# bend_it_board_v_2_F.net
KiCad netlist of a schematic drawn in EAGLE
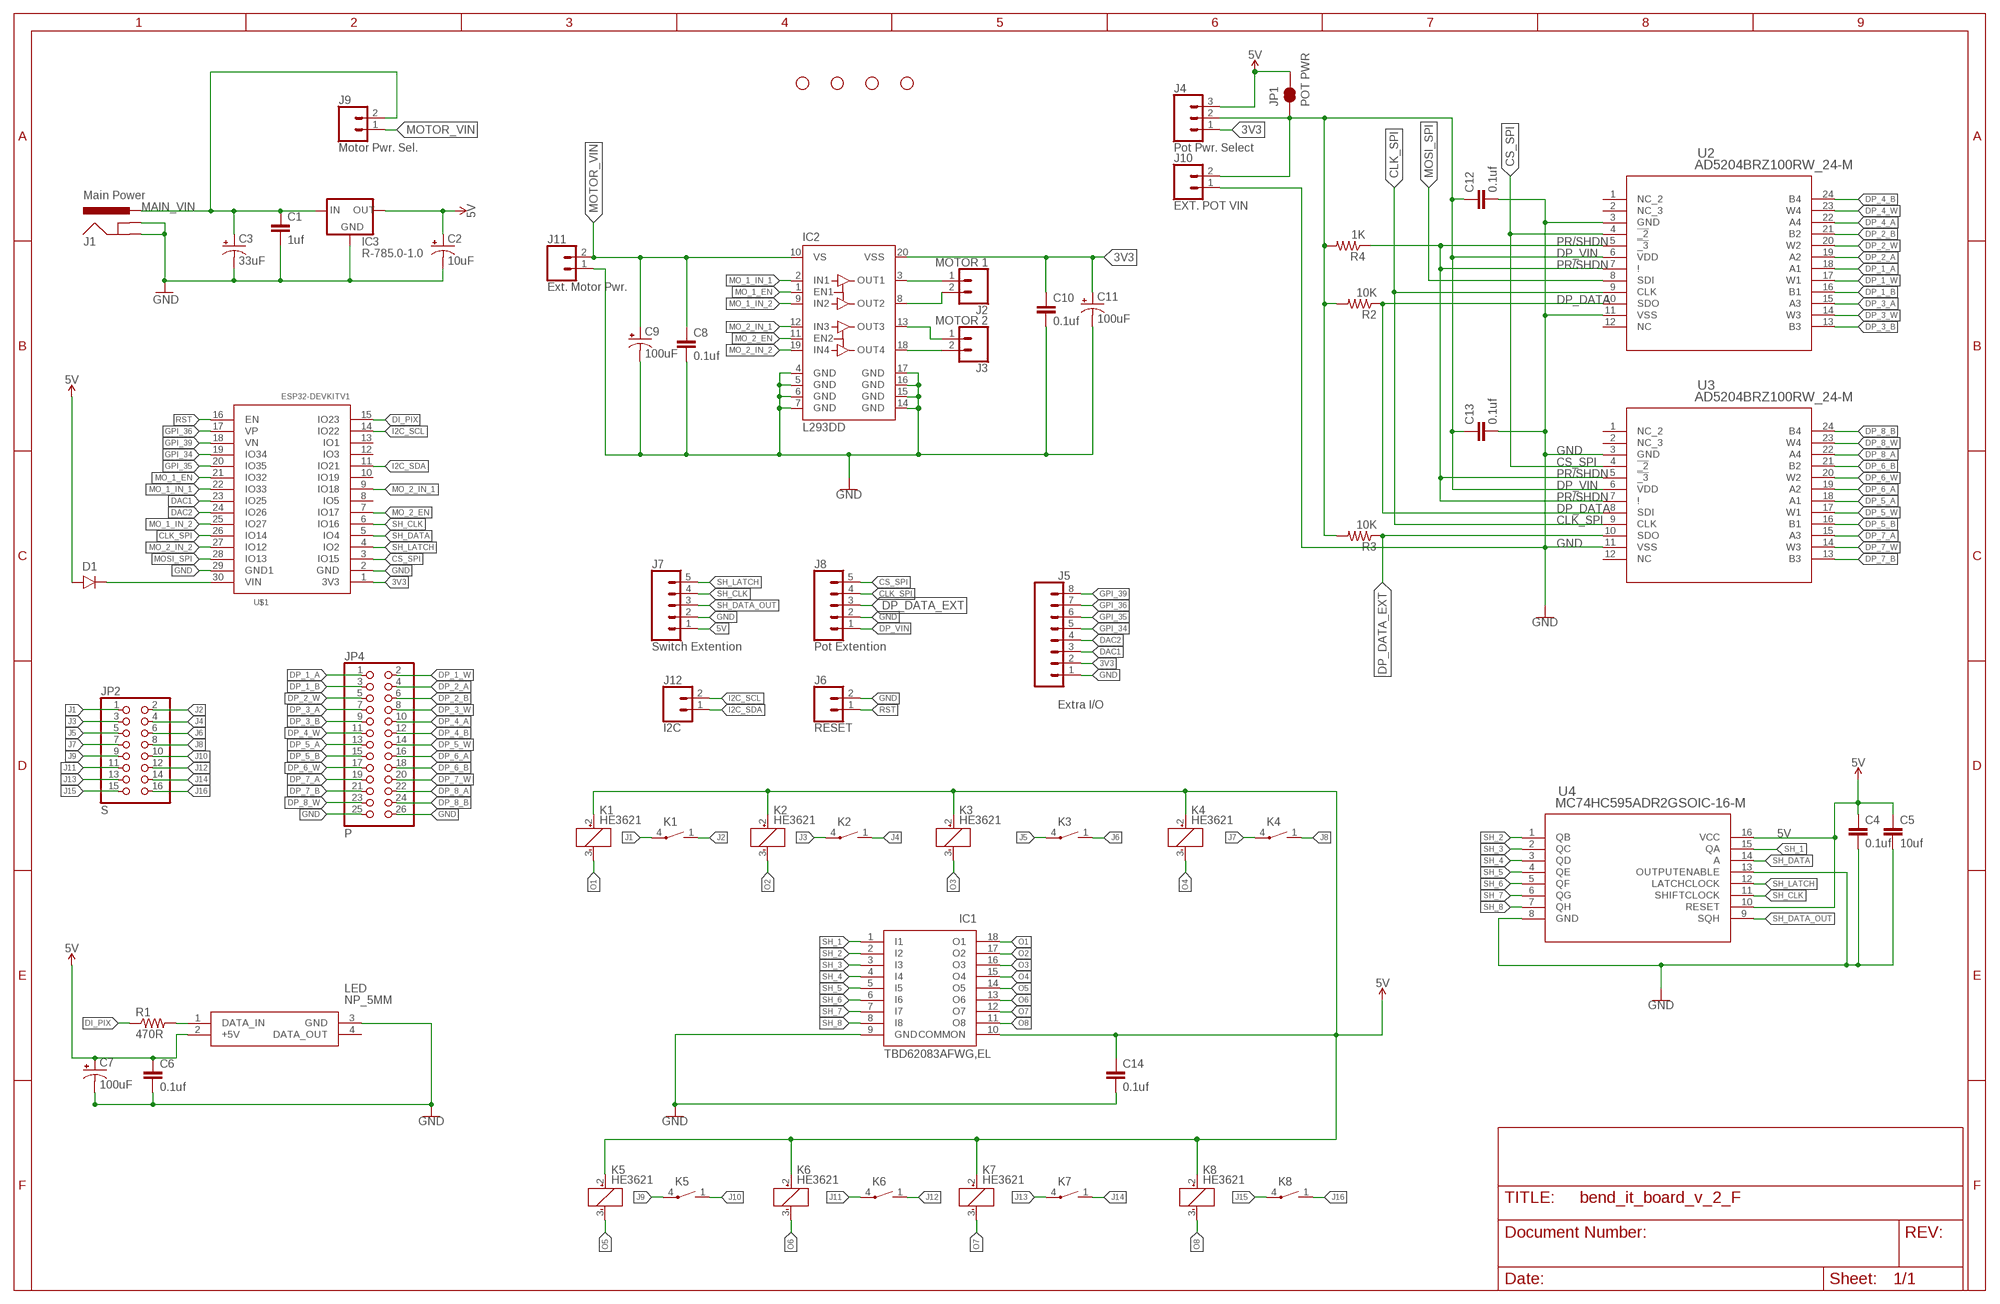
[diagram p0: schematic, sheet 1]

(export (version "E")
  (design (tool "Eeschema 10.0.6"))
  (components
    (comp (ref "C1")
      (value "1uf")
      (footprint "eagle-import:C0805")
      (libsource (lib "eagle-import") (part "C-EUC0805"))
    )
    (comp (ref "C2")
      (value "10uF")
      (footprint "eagle-import:PANASONIC_B")
      (libsource (lib "eagle-import") (part "CPOL-USB"))
    )
    (comp (ref "C3")
      (value "33uF")
      (footprint "eagle-import:PANASONIC_D")
      (libsource (lib "eagle-import") (part "CPOL-USD"))
    )
    (comp (ref "C4")
      (value "0.1uf")
      (footprint "eagle-import:C0805")
      (libsource (lib "eagle-import") (part "C-EUC0805"))
    )
    (comp (ref "C5")
      (value "10uf")
      (footprint "eagle-import:C0805")
      (libsource (lib "eagle-import") (part "C-EUC0805"))
    )
    (comp (ref "C6")
      (value "0.1uf")
      (footprint "eagle-import:C0805")
      (libsource (lib "eagle-import") (part "C-EUC0805"))
    )
    (comp (ref "C7")
      (value "100uF")
      (footprint "eagle-import:PANASONIC_D")
      (libsource (lib "eagle-import") (part "CPOL-USD"))
    )
    (comp (ref "C8")
      (value "0.1uf")
      (footprint "eagle-import:C0805")
      (libsource (lib "eagle-import") (part "C-EUC0805"))
    )
    (comp (ref "C9")
      (value "100uF")
      (footprint "eagle-import:PANASONIC_D")
      (libsource (lib "eagle-import") (part "CPOL-USD"))
    )
    (comp (ref "C10")
      (value "0.1uf")
      (footprint "eagle-import:C0805")
      (libsource (lib "eagle-import") (part "C-EUC0805"))
    )
    (comp (ref "C11")
      (value "100uF")
      (footprint "eagle-import:PANASONIC_D")
      (libsource (lib "eagle-import") (part "CPOL-USD"))
    )
    (comp (ref "C12")
      (value "0.1uf")
      (footprint "eagle-import:C0805")
      (libsource (lib "eagle-import") (part "C-EUC0805"))
    )
    (comp (ref "C13")
      (value "0.1uf")
      (footprint "eagle-import:C0805")
      (libsource (lib "eagle-import") (part "C-EUC0805"))
    )
    (comp (ref "C14")
      (value "0.1uf")
      (footprint "eagle-import:C0805")
      (libsource (lib "eagle-import") (part "C-EUC0805"))
    )
    (comp (ref "D1")
      (value "1N4001")
      (footprint "eagle-import:DO41-10")
      (libsource (lib "eagle-import") (part "1N4001"))
    )
    (comp (ref "H1")
      (value "STAND-OFF")
      (footprint "eagle-import:STAND-OFF")
      (libsource (lib "eagle-import") (part "STAND-OFF"))
    )
    (comp (ref "H2")
      (value "STAND-OFF")
      (footprint "eagle-import:STAND-OFF")
      (libsource (lib "eagle-import") (part "STAND-OFF"))
    )
    (comp (ref "H3")
      (value "STAND-OFF")
      (footprint "eagle-import:STAND-OFF")
      (libsource (lib "eagle-import") (part "STAND-OFF"))
    )
    (comp (ref "H4")
      (value "STAND-OFF")
      (footprint "eagle-import:STAND-OFF")
      (libsource (lib "eagle-import") (part "STAND-OFF"))
    )
    (comp (ref "IC1")
      (value "TBD62083AFWG,EL")
      (footprint "eagle-import:SOIC127P1032X285-18N")
      (fields
        (field (name "MANUFACTURER_PART_NUMBER") "TBD62083AFWG,EL")
        (field (name "MOUSER_PART_NUMBER") "757-TBD62083AFWGEL")
      )
      (libsource (lib "eagle-import") (part "TBD62083AFWG,EL"))
    )
    (comp (ref "IC2")
      (value "L293DD")
      (footprint "eagle-import:SO20")
      (libsource (lib "eagle-import") (part "L293DD"))
    )
    (comp (ref "IC3")
      (value "R-785.0-1.0")
      (footprint "eagle-import:SIP3")
      (fields (field (name "MF") "Recom"))
      (libsource (lib "eagle-import") (part "R-78-1.05.0"))
    )
    (comp (ref "J1")
      (value "Main Power")
      (footprint "eagle-import:POWER_JACK_PTH")
      (libsource (lib "eagle-import") (part "POWER_JACK"))
    )
    (comp (ref "J2")
      (value "MOTOR 1")
      (footprint "eagle-import:SCREWTERMINAL-5MM-2")
      (libsource (lib "eagle-import") (part "CONN_025MM"))
    )
    (comp (ref "J3")
      (value "MOTOR 2")
      (footprint "eagle-import:SCREWTERMINAL-5MM-2")
      (libsource (lib "eagle-import") (part "CONN_025MM"))
    )
    (comp (ref "J4")
      (value "Pot Pwr. Select")
      (footprint "eagle-import:1X03")
      (libsource (lib "eagle-import") (part "CONN_03"))
    )
    (comp (ref "J5")
      (value "Extra I/O")
      (footprint "eagle-import:1X08")
      (libsource (lib "eagle-import") (part "CONN_08{dblquote}"))
    )
    (comp (ref "J6")
      (value "RESET")
      (footprint "eagle-import:1X02")
      (libsource (lib "eagle-import") (part "CONN_02"))
    )
    (comp (ref "J7")
      (value "Switch Extention")
      (footprint "eagle-import:1X05")
      (libsource (lib "eagle-import") (part "CONN_05"))
    )
    (comp (ref "J8")
      (value "Pot Extention")
      (footprint "eagle-import:1X05")
      (libsource (lib "eagle-import") (part "CONN_05"))
    )
    (comp (ref "J9")
      (value "Motor Pwr. Sel.")
      (footprint "eagle-import:1X02")
      (libsource (lib "eagle-import") (part "CONN_02"))
    )
    (comp (ref "J10")
      (value "EXT. POT VIN")
      (footprint "eagle-import:1X02_LOCK_LONGPADS")
      (libsource (lib "eagle-import") (part "CONN_02LOCK_LONGPADS"))
    )
    (comp (ref "J11")
      (value "Ext. Motor Pwr.")
      (footprint "eagle-import:1X02_LOCK_LONGPADS")
      (libsource (lib "eagle-import") (part "CONN_02LOCK_LONGPADS"))
    )
    (comp (ref "J12")
      (value "I2C")
      (footprint "eagle-import:1X02")
      (libsource (lib "eagle-import") (part "CONN_02"))
    )
    (comp (ref "JP1")
      (value "POT PWR")
      (footprint "eagle-import:SMT-JUMPER_2_NC_TRACE_SILK")
      (libsource (lib "eagle-import") (part "JUMPER-SMT_2_NC_TRACE_SILK"))
    )
    (comp (ref "JP2")
      (value "S")
      (footprint "eagle-import:2X08")
      (libsource (lib "eagle-import") (part "PINHD-2X8"))
    )
    (comp (ref "JP4")
      (value "P")
      (footprint "eagle-import:2X13")
      (libsource (lib "eagle-import") (part "PINHD-2X13"))
    )
    (comp (ref "K1")
      (value "HE3621")
      (footprint "eagle-import:HE3621")
      (fields (field (name "MF") "HAMLIN") (field (name "MPN") "HE3621A2410"))
      (libsource (lib "eagle-import") (part "HE3621"))
    )
    (comp (ref "K2")
      (value "HE3621")
      (footprint "eagle-import:HE3621")
      (fields (field (name "MF") "HAMLIN") (field (name "MPN") "HE3621A2410"))
      (libsource (lib "eagle-import") (part "HE3621"))
    )
    (comp (ref "K3")
      (value "HE3621")
      (footprint "eagle-import:HE3621")
      (fields (field (name "MF") "HAMLIN") (field (name "MPN") "HE3621A2410"))
      (libsource (lib "eagle-import") (part "HE3621"))
    )
    (comp (ref "K4")
      (value "HE3621")
      (footprint "eagle-import:HE3621")
      (fields (field (name "MF") "HAMLIN") (field (name "MPN") "HE3621A2410"))
      (libsource (lib "eagle-import") (part "HE3621"))
    )
    (comp (ref "K5")
      (value "HE3621")
      (footprint "eagle-import:HE3621")
      (fields (field (name "MF") "HAMLIN") (field (name "MPN") "HE3621A2410"))
      (libsource (lib "eagle-import") (part "HE3621"))
    )
    (comp (ref "K6")
      (value "HE3621")
      (footprint "eagle-import:HE3621")
      (fields (field (name "MF") "HAMLIN") (field (name "MPN") "HE3621A2410"))
      (libsource (lib "eagle-import") (part "HE3621"))
    )
    (comp (ref "K7")
      (value "HE3621")
      (footprint "eagle-import:HE3621")
      (fields (field (name "MF") "HAMLIN") (field (name "MPN") "HE3621A2410"))
      (libsource (lib "eagle-import") (part "HE3621"))
    )
    (comp (ref "K8")
      (value "HE3621")
      (footprint "eagle-import:HE3621")
      (fields (field (name "MF") "HAMLIN") (field (name "MPN") "HE3621A2410"))
      (libsource (lib "eagle-import") (part "HE3621"))
    )
    (comp (ref "LED")
      (value "NP_5MM")
      (footprint "eagle-import:1938")
      (fields (field (name "MANUFACTURER_PART_NUMBER") "1938") (field (name "MOUSER_PART_NUMBER") "485-1938"))
      (libsource (lib "eagle-import") (part "1938"))
    )
    (comp (ref "R1")
      (value "470R")
      (footprint "eagle-import:R0805")
      (libsource (lib "eagle-import") (part "R-US_R0805"))
    )
    (comp (ref "R2")
      (value "10K")
      (footprint "eagle-import:R0805")
      (libsource (lib "eagle-import") (part "R-US_R0805"))
    )
    (comp (ref "R3")
      (value "10K")
      (footprint "eagle-import:R0805")
      (libsource (lib "eagle-import") (part "R-US_R0805"))
    )
    (comp (ref "R4")
      (value "1K")
      (footprint "eagle-import:R0805")
      (libsource (lib "eagle-import") (part "R-US_R0805"))
    )
    (comp (ref "U$1")
      (value "ESP32DEVKITV1")
      (footprint "eagle-import:ESP32-DEVKITV1")
      (libsource (lib "eagle-import") (part "ESP32DEVKITV1"))
    )
    (comp (ref "U2")
      (value "AD5204BRZ100RW_24-M")
      (footprint "eagle-import:RW_24-M")
      (fields (field (name "MANUFACTURER_PART_NUMBER") "AD5204BRZ100"))
      (libsource (lib "eagle-import") (part "AD5204BRZ100RW_24-M"))
    )
    (comp (ref "U3")
      (value "AD5204BRZ100RW_24-M")
      (footprint "eagle-import:RW_24-M")
      (fields (field (name "MANUFACTURER_PART_NUMBER") "AD5204BRZ100"))
      (libsource (lib "eagle-import") (part "AD5204BRZ100RW_24-M"))
    )
    (comp (ref "U4")
      (value "MC74HC595ADR2GSOIC-16-M")
      (footprint "eagle-import:SOIC-16-M")
      (fields (field (name "MANUFACTURER_PART_NUMBER") "MC74HC595ADR2G"))
      (libsource (lib "eagle-import") (part "MC74HC595ADR2GSOIC-16-M"))
    )
  )
  (nets
    (net (code "1") (name "/DP_DATA") (class "Default")
      (node (ref "R2") (pin "1") (pinfunction "1_1") (pintype "passive"))
      (node (ref "U2") (pin "10") (pinfunction "SDO_10") (pintype "passive"))
      (node (ref "U3") (pin "8") (pinfunction "SDI_8") (pintype "passive"))
    )
    (net (code "2") (name "/MAIN_VIN") (class "Default")
      (node (ref "C1") (pin "1") (pinfunction "1_1") (pintype "passive"))
      (node (ref "C3") (pin "+") (pinfunction "+_+") (pintype "passive"))
      (node (ref "IC3") (pin "1") (pinfunction "IN_1") (pintype "input"))
      (node (ref "J1") (pin "PWR") (pinfunction "PWR_PWR") (pintype "bidirectional"))
      (node (ref "J9") (pin "2") (pinfunction "2_2") (pintype "passive"))
    )
    (net (code "3") (name "/PR{slash}SHDN") (class "Default")
      (node (ref "R4") (pin "1") (pinfunction "1_1") (pintype "passive"))
      (node (ref "U2") (pin "5") (pinfunction "~{_3}_5") (pintype "passive"))
      (node (ref "U2") (pin "7") (pinfunction "~_7") (pintype "passive"))
      (node (ref "U3") (pin "5") (pinfunction "~{_3}_5") (pintype "passive"))
      (node (ref "U3") (pin "7") (pinfunction "~_7") (pintype "passive"))
    )
    (net (code "4") (name "3V3") (class "Default")
      (node (ref "C10") (pin "1") (pinfunction "1_1") (pintype "passive"))
      (node (ref "C11") (pin "+") (pinfunction "+_+") (pintype "passive"))
      (node (ref "IC2") (pin "20") (pinfunction "VSS_20") (pintype "power_in"))
      (node (ref "J4") (pin "1") (pinfunction "1_1") (pintype "passive"))
      (node (ref "J5") (pin "2") (pinfunction "2_2") (pintype "passive"))
      (node (ref "U$1") (pin "1") (pinfunction "3V3_1") (pintype "bidirectional"))
    )
    (net (code "5") (name "5V") (class "Default")
      (node (ref "C14") (pin "1") (pinfunction "1_1") (pintype "passive"))
      (node (ref "C2") (pin "+") (pinfunction "+_+") (pintype "passive"))
      (node (ref "C4") (pin "1") (pinfunction "1_1") (pintype "passive"))
      (node (ref "C5") (pin "1") (pinfunction "1_1") (pintype "passive"))
      (node (ref "C6") (pin "1") (pinfunction "1_1") (pintype "passive"))
      (node (ref "C7") (pin "+") (pinfunction "+_+") (pintype "passive"))
      (node (ref "D1") (pin "A") (pinfunction "ANODE_A") (pintype "passive"))
      (node (ref "IC1") (pin "10") (pinfunction "COMMON_10") (pintype "bidirectional"))
      (node (ref "IC3") (pin "3") (pinfunction "OUT_3") (pintype "passive"))
      (node (ref "J4") (pin "3") (pinfunction "3_3") (pintype "passive"))
      (node (ref "J7") (pin "1") (pinfunction "1_1") (pintype "passive"))
      (node (ref "JP1") (pin "2") (pinfunction "2_2") (pintype "passive"))
      (node (ref "K1") (pin "2") (pinfunction "+_2") (pintype "passive"))
      (node (ref "K2") (pin "2") (pinfunction "+_2") (pintype "passive"))
      (node (ref "K3") (pin "2") (pinfunction "+_2") (pintype "passive"))
      (node (ref "K4") (pin "2") (pinfunction "+_2") (pintype "passive"))
      (node (ref "K5") (pin "2") (pinfunction "+_2") (pintype "passive"))
      (node (ref "K6") (pin "2") (pinfunction "+_2") (pintype "passive"))
      (node (ref "K7") (pin "2") (pinfunction "+_2") (pintype "passive"))
      (node (ref "K8") (pin "2") (pinfunction "+_2") (pintype "passive"))
      (node (ref "LED") (pin "2") (pinfunction "+5V_2") (pintype "bidirectional"))
      (node (ref "U4") (pin "10") (pinfunction "RESET_10") (pintype "input"))
      (node (ref "U4") (pin "16") (pinfunction "VCC_16") (pintype "power_in"))
    )
    (net (code "6") (name "CLK_SPI") (class "Default")
      (node (ref "J8") (pin "4") (pinfunction "4_4") (pintype "passive"))
      (node (ref "U$1") (pin "26") (pinfunction "IO14_26") (pintype "bidirectional"))
      (node (ref "U2") (pin "9") (pinfunction "CLK_9") (pintype "passive"))
      (node (ref "U3") (pin "9") (pinfunction "CLK_9") (pintype "passive"))
    )
    (net (code "7") (name "CS_SPI") (class "Default")
      (node (ref "J8") (pin "5") (pinfunction "5_5") (pintype "passive"))
      (node (ref "U$1") (pin "3") (pinfunction "IO15_3") (pintype "bidirectional"))
      (node (ref "U2") (pin "4") (pinfunction "~{_2}_4") (pintype "passive"))
      (node (ref "U3") (pin "4") (pinfunction "~{_2}_4") (pintype "passive"))
    )
    (net (code "8") (name "DAC1") (class "Default")
      (node (ref "J5") (pin "3") (pinfunction "3_3") (pintype "passive"))
      (node (ref "U$1") (pin "23") (pinfunction "IO25_23") (pintype "bidirectional"))
    )
    (net (code "9") (name "DAC2") (class "Default")
      (node (ref "J5") (pin "4") (pinfunction "4_4") (pintype "passive"))
      (node (ref "U$1") (pin "24") (pinfunction "IO26_24") (pintype "bidirectional"))
    )
    (net (code "10") (name "DI_PIX") (class "Default")
      (node (ref "R1") (pin "1") (pinfunction "1_1") (pintype "passive"))
      (node (ref "U$1") (pin "15") (pinfunction "IO23_15") (pintype "bidirectional"))
    )
    (net (code "11") (name "DP_1_A") (class "Default")
      (node (ref "JP4") (pin "1") (pinfunction "1_1") (pintype "passive"))
      (node (ref "U2") (pin "18") (pinfunction "A1_18") (pintype "passive"))
    )
    (net (code "12") (name "DP_1_B") (class "Default")
      (node (ref "JP4") (pin "3") (pinfunction "3_3") (pintype "passive"))
      (node (ref "U2") (pin "16") (pinfunction "B1_16") (pintype "passive"))
    )
    (net (code "13") (name "DP_1_W") (class "Default")
      (node (ref "JP4") (pin "2") (pinfunction "2_2") (pintype "passive"))
      (node (ref "U2") (pin "17") (pinfunction "W1_17") (pintype "passive"))
    )
    (net (code "14") (name "DP_2_A") (class "Default")
      (node (ref "JP4") (pin "4") (pinfunction "4_4") (pintype "passive"))
      (node (ref "U2") (pin "19") (pinfunction "A2_19") (pintype "passive"))
    )
    (net (code "15") (name "DP_2_B") (class "Default")
      (node (ref "JP4") (pin "6") (pinfunction "6_6") (pintype "passive"))
      (node (ref "U2") (pin "21") (pinfunction "B2_21") (pintype "passive"))
    )
    (net (code "16") (name "DP_2_W") (class "Default")
      (node (ref "JP4") (pin "5") (pinfunction "5_5") (pintype "passive"))
      (node (ref "U2") (pin "20") (pinfunction "W2_20") (pintype "passive"))
    )
    (net (code "17") (name "DP_3_A") (class "Default")
      (node (ref "JP4") (pin "7") (pinfunction "7_7") (pintype "passive"))
      (node (ref "U2") (pin "15") (pinfunction "A3_15") (pintype "passive"))
    )
    (net (code "18") (name "DP_3_B") (class "Default")
      (node (ref "JP4") (pin "9") (pinfunction "9_9") (pintype "passive"))
      (node (ref "U2") (pin "13") (pinfunction "B3_13") (pintype "passive"))
    )
    (net (code "19") (name "DP_3_W") (class "Default")
      (node (ref "JP4") (pin "8") (pinfunction "8_8") (pintype "passive"))
      (node (ref "U2") (pin "14") (pinfunction "W3_14") (pintype "passive"))
    )
    (net (code "20") (name "DP_4_A") (class "Default")
      (node (ref "JP4") (pin "10") (pinfunction "10_10") (pintype "passive"))
      (node (ref "U2") (pin "22") (pinfunction "A4_22") (pintype "passive"))
    )
    (net (code "21") (name "DP_4_B") (class "Default")
      (node (ref "JP4") (pin "12") (pinfunction "12_12") (pintype "passive"))
      (node (ref "U2") (pin "24") (pinfunction "B4_24") (pintype "passive"))
    )
    (net (code "22") (name "DP_4_W") (class "Default")
      (node (ref "JP4") (pin "11") (pinfunction "11_11") (pintype "passive"))
      (node (ref "U2") (pin "23") (pinfunction "W4_23") (pintype "passive"))
    )
    (net (code "23") (name "DP_5_A") (class "Default")
      (node (ref "JP4") (pin "13") (pinfunction "13_13") (pintype "passive"))
      (node (ref "U3") (pin "18") (pinfunction "A1_18") (pintype "passive"))
    )
    (net (code "24") (name "DP_5_B") (class "Default")
      (node (ref "JP4") (pin "15") (pinfunction "15_15") (pintype "passive"))
      (node (ref "U3") (pin "16") (pinfunction "B1_16") (pintype "passive"))
    )
    (net (code "25") (name "DP_5_W") (class "Default")
      (node (ref "JP4") (pin "14") (pinfunction "14_14") (pintype "passive"))
      (node (ref "U3") (pin "17") (pinfunction "W1_17") (pintype "passive"))
    )
    (net (code "26") (name "DP_6_A") (class "Default")
      (node (ref "JP4") (pin "16") (pinfunction "16_16") (pintype "passive"))
      (node (ref "U3") (pin "19") (pinfunction "A2_19") (pintype "passive"))
    )
    (net (code "27") (name "DP_6_B") (class "Default")
      (node (ref "JP4") (pin "18") (pinfunction "18_18") (pintype "passive"))
      (node (ref "U3") (pin "21") (pinfunction "B2_21") (pintype "passive"))
    )
    (net (code "28") (name "DP_6_W") (class "Default")
      (node (ref "JP4") (pin "17") (pinfunction "17_17") (pintype "passive"))
      (node (ref "U3") (pin "20") (pinfunction "W2_20") (pintype "passive"))
    )
    (net (code "29") (name "DP_7_A") (class "Default")
      (node (ref "JP4") (pin "19") (pinfunction "19_19") (pintype "passive"))
      (node (ref "U3") (pin "15") (pinfunction "A3_15") (pintype "passive"))
    )
    (net (code "30") (name "DP_7_B") (class "Default")
      (node (ref "JP4") (pin "21") (pinfunction "21_21") (pintype "passive"))
      (node (ref "U3") (pin "13") (pinfunction "B3_13") (pintype "passive"))
    )
    (net (code "31") (name "DP_7_W") (class "Default")
      (node (ref "JP4") (pin "20") (pinfunction "20_20") (pintype "passive"))
      (node (ref "U3") (pin "14") (pinfunction "W3_14") (pintype "passive"))
    )
    (net (code "32") (name "DP_8_A") (class "Default")
      (node (ref "JP4") (pin "22") (pinfunction "22_22") (pintype "passive"))
      (node (ref "U3") (pin "22") (pinfunction "A4_22") (pintype "passive"))
    )
    (net (code "33") (name "DP_8_B") (class "Default")
      (node (ref "JP4") (pin "24") (pinfunction "24_24") (pintype "passive"))
      (node (ref "U3") (pin "24") (pinfunction "B4_24") (pintype "passive"))
    )
    (net (code "34") (name "DP_8_W") (class "Default")
      (node (ref "JP4") (pin "23") (pinfunction "23_23") (pintype "passive"))
      (node (ref "U3") (pin "23") (pinfunction "W4_23") (pintype "passive"))
    )
    (net (code "35") (name "DP_DATA_EXT") (class "Default")
      (node (ref "J8") (pin "3") (pinfunction "3_3") (pintype "passive"))
      (node (ref "R3") (pin "1") (pinfunction "1_1") (pintype "passive"))
      (node (ref "U3") (pin "10") (pinfunction "SDO_10") (pintype "passive"))
    )
    (net (code "36") (name "DP_VIN") (class "Default")
      (node (ref "C12") (pin "1") (pinfunction "1_1") (pintype "passive"))
      (node (ref "C13") (pin "1") (pinfunction "1_1") (pintype "passive"))
      (node (ref "J10") (pin "2") (pinfunction "2_2") (pintype "passive"))
      (node (ref "J4") (pin "2") (pinfunction "2_2") (pintype "passive"))
      (node (ref "J8") (pin "1") (pinfunction "1_1") (pintype "passive"))
      (node (ref "JP1") (pin "1") (pinfunction "1_1") (pintype "passive"))
      (node (ref "R2") (pin "2") (pinfunction "2_2") (pintype "passive"))
      (node (ref "R3") (pin "2") (pinfunction "2_2") (pintype "passive"))
      (node (ref "R4") (pin "2") (pinfunction "2_2") (pintype "passive"))
      (node (ref "U2") (pin "6") (pinfunction "VDD_6") (pintype "power_in"))
      (node (ref "U3") (pin "6") (pinfunction "VDD_6") (pintype "power_in"))
    )
    (net (code "37") (name "GND") (class "Default")
      (node (ref "C1") (pin "2") (pinfunction "2_2") (pintype "passive"))
      (node (ref "C10") (pin "2") (pinfunction "2_2") (pintype "passive"))
      (node (ref "C11") (pin "-") (pinfunction "-_-") (pintype "passive"))
      (node (ref "C12") (pin "2") (pinfunction "2_2") (pintype "passive"))
      (node (ref "C13") (pin "2") (pinfunction "2_2") (pintype "passive"))
      (node (ref "C14") (pin "2") (pinfunction "2_2") (pintype "passive"))
      (node (ref "C2") (pin "-") (pinfunction "-_-") (pintype "passive"))
      (node (ref "C3") (pin "-") (pinfunction "-_-") (pintype "passive"))
      (node (ref "C4") (pin "2") (pinfunction "2_2") (pintype "passive"))
      (node (ref "C5") (pin "2") (pinfunction "2_2") (pintype "passive"))
      (node (ref "C6") (pin "2") (pinfunction "2_2") (pintype "passive"))
      (node (ref "C7") (pin "-") (pinfunction "-_-") (pintype "passive"))
      (node (ref "C8") (pin "2") (pinfunction "2_2") (pintype "passive"))
      (node (ref "C9") (pin "-") (pinfunction "-_-") (pintype "passive"))
      (node (ref "IC1") (pin "9") (pinfunction "GND_9") (pintype "bidirectional"))
      (node (ref "IC2") (pin "14") (pinfunction "GND_14") (pintype "power_in"))
      (node (ref "IC2") (pin "15") (pinfunction "GND_15") (pintype "power_in"))
      (node (ref "IC2") (pin "16") (pinfunction "GND_16") (pintype "power_in"))
      (node (ref "IC2") (pin "17") (pinfunction "GND_17") (pintype "power_in"))
      (node (ref "IC2") (pin "4") (pinfunction "GND_4") (pintype "power_in"))
      (node (ref "IC2") (pin "5") (pinfunction "GND_5") (pintype "power_in"))
      (node (ref "IC2") (pin "6") (pinfunction "GND_6") (pintype "power_in"))
      (node (ref "IC2") (pin "7") (pinfunction "GND_7") (pintype "power_in"))
      (node (ref "IC3") (pin "2") (pinfunction "GND_2") (pintype "input"))
      (node (ref "J1") (pin "GND") (pinfunction "GND_GND") (pintype "bidirectional"))
      (node (ref "J1") (pin "GNDBREAK") (pinfunction "GNDBREAK_GNDBREAK") (pintype "bidirectional"))
      (node (ref "J10") (pin "1") (pinfunction "1_1") (pintype "passive"))
      (node (ref "J11") (pin "1") (pinfunction "1_1") (pintype "passive"))
      (node (ref "J5") (pin "1") (pinfunction "1_1") (pintype "passive"))
      (node (ref "J6") (pin "2") (pinfunction "2_2") (pintype "passive"))
      (node (ref "J7") (pin "2") (pinfunction "2_2") (pintype "passive"))
      (node (ref "J8") (pin "2") (pinfunction "2_2") (pintype "passive"))
      (node (ref "JP4") (pin "25") (pinfunction "25_25") (pintype "passive"))
      (node (ref "JP4") (pin "26") (pinfunction "26_26") (pintype "passive"))
      (node (ref "LED") (pin "3") (pinfunction "GND_3") (pintype "bidirectional"))
      (node (ref "U$1") (pin "2") (pinfunction "GND_2") (pintype "bidirectional"))
      (node (ref "U$1") (pin "29") (pinfunction "GND1_29") (pintype "bidirectional"))
      (node (ref "U2") (pin "11") (pinfunction "VSS_11") (pintype "power_in"))
      (node (ref "U2") (pin "3") (pinfunction "GND_3") (pintype "passive"))
      (node (ref "U3") (pin "11") (pinfunction "VSS_11") (pintype "power_in"))
      (node (ref "U3") (pin "3") (pinfunction "GND_3") (pintype "passive"))
      (node (ref "U4") (pin "13") (pinfunction "OUTPUTENABLE_13") (pintype "bidirectional"))
      (node (ref "U4") (pin "8") (pinfunction "GND_8") (pintype "power_in"))
    )
    (net (code "38") (name "GPI_34") (class "Default")
      (node (ref "J5") (pin "5") (pinfunction "5_5") (pintype "passive"))
      (node (ref "U$1") (pin "19") (pinfunction "IO34_19") (pintype "bidirectional"))
    )
    (net (code "39") (name "GPI_35") (class "Default")
      (node (ref "J5") (pin "6") (pinfunction "6_6") (pintype "passive"))
      (node (ref "U$1") (pin "20") (pinfunction "IO35_20") (pintype "bidirectional"))
    )
    (net (code "40") (name "GPI_36") (class "Default")
      (node (ref "J5") (pin "7") (pinfunction "7_7") (pintype "passive"))
      (node (ref "U$1") (pin "17") (pinfunction "VP_17") (pintype "bidirectional"))
    )
    (net (code "41") (name "GPI_39") (class "Default")
      (node (ref "J5") (pin "8") (pinfunction "8_8") (pintype "passive"))
      (node (ref "U$1") (pin "18") (pinfunction "VN_18") (pintype "bidirectional"))
    )
    (net (code "42") (name "I2C_SCL") (class "Default")
      (node (ref "J12") (pin "2") (pinfunction "2_2") (pintype "passive"))
      (node (ref "U$1") (pin "14") (pinfunction "IO22_14") (pintype "bidirectional"))
    )
    (net (code "43") (name "I2C_SDA") (class "Default")
      (node (ref "J12") (pin "1") (pinfunction "1_1") (pintype "passive"))
      (node (ref "U$1") (pin "11") (pinfunction "IO21_11") (pintype "bidirectional"))
    )
    (net (code "44") (name "J1") (class "Default")
      (node (ref "JP2") (pin "1") (pinfunction "1_1") (pintype "passive"))
      (node (ref "K1") (pin "4") (pinfunction "P_4") (pintype "passive"))
    )
    (net (code "45") (name "J2") (class "Default")
      (node (ref "JP2") (pin "2") (pinfunction "2_2") (pintype "passive"))
      (node (ref "K1") (pin "1") (pinfunction "S_1") (pintype "passive"))
    )
    (net (code "46") (name "J3") (class "Default")
      (node (ref "JP2") (pin "3") (pinfunction "3_3") (pintype "passive"))
      (node (ref "K2") (pin "4") (pinfunction "P_4") (pintype "passive"))
    )
    (net (code "47") (name "J4") (class "Default")
      (node (ref "JP2") (pin "4") (pinfunction "4_4") (pintype "passive"))
      (node (ref "K2") (pin "1") (pinfunction "S_1") (pintype "passive"))
    )
    (net (code "48") (name "J5") (class "Default")
      (node (ref "JP2") (pin "5") (pinfunction "5_5") (pintype "passive"))
      (node (ref "K3") (pin "4") (pinfunction "P_4") (pintype "passive"))
    )
    (net (code "49") (name "J6") (class "Default")
      (node (ref "JP2") (pin "6") (pinfunction "6_6") (pintype "passive"))
      (node (ref "K3") (pin "1") (pinfunction "S_1") (pintype "passive"))
    )
    (net (code "50") (name "J7") (class "Default")
      (node (ref "JP2") (pin "7") (pinfunction "7_7") (pintype "passive"))
      (node (ref "K4") (pin "4") (pinfunction "P_4") (pintype "passive"))
    )
    (net (code "51") (name "J8") (class "Default")
      (node (ref "JP2") (pin "8") (pinfunction "8_8") (pintype "passive"))
      (node (ref "K4") (pin "1") (pinfunction "S_1") (pintype "passive"))
    )
    (net (code "52") (name "J9") (class "Default")
      (node (ref "JP2") (pin "9") (pinfunction "9_9") (pintype "passive"))
      (node (ref "K5") (pin "4") (pinfunction "P_4") (pintype "passive"))
    )
    (net (code "53") (name "J10") (class "Default")
      (node (ref "JP2") (pin "10") (pinfunction "10_10") (pintype "passive"))
      (node (ref "K5") (pin "1") (pinfunction "S_1") (pintype "passive"))
    )
    (net (code "54") (name "J11") (class "Default")
      (node (ref "JP2") (pin "11") (pinfunction "11_11") (pintype "passive"))
      (node (ref "K6") (pin "4") (pinfunction "P_4") (pintype "passive"))
    )
    (net (code "55") (name "J12") (class "Default")
      (node (ref "JP2") (pin "12") (pinfunction "12_12") (pintype "passive"))
      (node (ref "K6") (pin "1") (pinfunction "S_1") (pintype "passive"))
    )
    (net (code "56") (name "J13") (class "Default")
      (node (ref "JP2") (pin "13") (pinfunction "13_13") (pintype "passive"))
      (node (ref "K7") (pin "4") (pinfunction "P_4") (pintype "passive"))
    )
    (net (code "57") (name "J14") (class "Default")
      (node (ref "JP2") (pin "14") (pinfunction "14_14") (pintype "passive"))
      (node (ref "K7") (pin "1") (pinfunction "S_1") (pintype "passive"))
    )
    (net (code "58") (name "J15") (class "Default")
      (node (ref "JP2") (pin "15") (pinfunction "15_15") (pintype "passive"))
      (node (ref "K8") (pin "4") (pinfunction "P_4") (pintype "passive"))
    )
    (net (code "59") (name "J16") (class "Default")
      (node (ref "JP2") (pin "16") (pinfunction "16_16") (pintype "passive"))
      (node (ref "K8") (pin "1") (pinfunction "S_1") (pintype "passive"))
    )
    (net (code "60") (name "MOSI_SPI") (class "Default")
      (node (ref "U$1") (pin "28") (pinfunction "IO13_28") (pintype "bidirectional"))
      (node (ref "U2") (pin "8") (pinfunction "SDI_8") (pintype "passive"))
    )
    (net (code "61") (name "MOTOR_VIN") (class "Default")
      (node (ref "C8") (pin "1") (pinfunction "1_1") (pintype "passive"))
      (node (ref "C9") (pin "+") (pinfunction "+_+") (pintype "passive"))
      (node (ref "IC2") (pin "10") (pinfunction "VS_10") (pintype "power_in"))
      (node (ref "J11") (pin "2") (pinfunction "2_2") (pintype "passive"))
      (node (ref "J9") (pin "1") (pinfunction "1_1") (pintype "passive"))
    )
    (net (code "62") (name "MO_1_EN") (class "Default")
      (node (ref "IC2") (pin "1") (pinfunction "EN1_1") (pintype "input"))
      (node (ref "U$1") (pin "21") (pinfunction "IO32_21") (pintype "bidirectional"))
    )
    (net (code "63") (name "MO_1_IN_1") (class "Default")
      (node (ref "IC2") (pin "2") (pinfunction "IN1_2") (pintype "input"))
      (node (ref "U$1") (pin "22") (pinfunction "IO33_22") (pintype "bidirectional"))
    )
    (net (code "64") (name "MO_1_IN_2") (class "Default")
      (node (ref "IC2") (pin "9") (pinfunction "IN2_9") (pintype "input"))
      (node (ref "U$1") (pin "25") (pinfunction "IO27_25") (pintype "bidirectional"))
    )
    (net (code "65") (name "MO_2_EN") (class "Default")
      (node (ref "IC2") (pin "11") (pinfunction "EN2_11") (pintype "input"))
      (node (ref "U$1") (pin "7") (pinfunction "IO17_7") (pintype "bidirectional"))
    )
    (net (code "66") (name "MO_2_IN_1") (class "Default")
      (node (ref "IC2") (pin "12") (pinfunction "IN3_12") (pintype "input"))
      (node (ref "U$1") (pin "9") (pinfunction "IO18_9") (pintype "bidirectional"))
    )
    (net (code "67") (name "MO_2_IN_2") (class "Default")
      (node (ref "IC2") (pin "19") (pinfunction "IN4_19") (pintype "input"))
      (node (ref "U$1") (pin "27") (pinfunction "IO12_27") (pintype "bidirectional"))
    )
    (net (code "68") (name "Net-(D1-CATHODE)") (class "Default")
      (node (ref "D1") (pin "C") (pinfunction "CATHODE_C") (pintype "passive"))
      (node (ref "U$1") (pin "30") (pinfunction "VIN_30") (pintype "bidirectional"))
    )
    (net (code "69") (name "Net-(IC2-OUT1)") (class "Default")
      (node (ref "IC2") (pin "3") (pinfunction "OUT1_3") (pintype "output"))
      (node (ref "J2") (pin "1") (pinfunction "1_1") (pintype "passive"))
    )
    (net (code "70") (name "Net-(IC2-OUT2)") (class "Default")
      (node (ref "IC2") (pin "8") (pinfunction "OUT2_8") (pintype "output"))
      (node (ref "J2") (pin "2") (pinfunction "2_2") (pintype "passive"))
    )
    (net (code "71") (name "Net-(IC2-OUT3)") (class "Default")
      (node (ref "IC2") (pin "13") (pinfunction "OUT3_13") (pintype "output"))
      (node (ref "J3") (pin "1") (pinfunction "1_1") (pintype "passive"))
    )
    (net (code "72") (name "Net-(IC2-OUT4)") (class "Default")
      (node (ref "IC2") (pin "18") (pinfunction "OUT4_18") (pintype "output"))
      (node (ref "J3") (pin "2") (pinfunction "2_2") (pintype "passive"))
    )
    (net (code "73") (name "Net-(LED-DATA_IN)") (class "Default")
      (node (ref "LED") (pin "1") (pinfunction "DATA_IN_1") (pintype "bidirectional"))
      (node (ref "R1") (pin "2") (pinfunction "2_2") (pintype "passive"))
    )
    (net (code "74") (name "O1") (class "Default")
      (node (ref "IC1") (pin "18") (pinfunction "O1_18") (pintype "bidirectional"))
      (node (ref "K1") (pin "3") (pinfunction "-_3") (pintype "passive"))
    )
    (net (code "75") (name "O2") (class "Default")
      (node (ref "IC1") (pin "17") (pinfunction "O2_17") (pintype "bidirectional"))
      (node (ref "K2") (pin "3") (pinfunction "-_3") (pintype "passive"))
    )
    (net (code "76") (name "O3") (class "Default")
      (node (ref "IC1") (pin "16") (pinfunction "O3_16") (pintype "bidirectional"))
      (node (ref "K3") (pin "3") (pinfunction "-_3") (pintype "passive"))
    )
    (net (code "77") (name "O4") (class "Default")
      (node (ref "IC1") (pin "15") (pinfunction "O4_15") (pintype "bidirectional"))
      (node (ref "K4") (pin "3") (pinfunction "-_3") (pintype "passive"))
    )
    (net (code "78") (name "O5") (class "Default")
      (node (ref "IC1") (pin "14") (pinfunction "O5_14") (pintype "bidirectional"))
      (node (ref "K5") (pin "3") (pinfunction "-_3") (pintype "passive"))
    )
    (net (code "79") (name "O6") (class "Default")
      (node (ref "IC1") (pin "13") (pinfunction "O6_13") (pintype "bidirectional"))
      (node (ref "K6") (pin "3") (pinfunction "-_3") (pintype "passive"))
    )
    (net (code "80") (name "O7") (class "Default")
      (node (ref "IC1") (pin "12") (pinfunction "O7_12") (pintype "bidirectional"))
      (node (ref "K7") (pin "3") (pinfunction "-_3") (pintype "passive"))
    )
    (net (code "81") (name "O8") (class "Default")
      (node (ref "IC1") (pin "11") (pinfunction "O8_11") (pintype "bidirectional"))
      (node (ref "K8") (pin "3") (pinfunction "-_3") (pintype "passive"))
    )
    (net (code "82") (name "RST") (class "Default")
      (node (ref "J6") (pin "1") (pinfunction "1_1") (pintype "passive"))
      (node (ref "U$1") (pin "16") (pinfunction "EN_16") (pintype "bidirectional"))
    )
    (net (code "83") (name "SH_1") (class "Default")
      (node (ref "IC1") (pin "1") (pinfunction "I1_1") (pintype "bidirectional"))
      (node (ref "U4") (pin "15") (pinfunction "QA_15") (pintype "output"))
    )
    (net (code "84") (name "SH_2") (class "Default")
      (node (ref "IC1") (pin "2") (pinfunction "I2_2") (pintype "bidirectional"))
      (node (ref "U4") (pin "1") (pinfunction "QB_1") (pintype "output"))
    )
    (net (code "85") (name "SH_3") (class "Default")
      (node (ref "IC1") (pin "3") (pinfunction "I3_3") (pintype "bidirectional"))
      (node (ref "U4") (pin "2") (pinfunction "QC_2") (pintype "output"))
    )
    (net (code "86") (name "SH_4") (class "Default")
      (node (ref "IC1") (pin "4") (pinfunction "I4_4") (pintype "bidirectional"))
      (node (ref "U4") (pin "3") (pinfunction "QD_3") (pintype "output"))
    )
    (net (code "87") (name "SH_5") (class "Default")
      (node (ref "IC1") (pin "5") (pinfunction "I5_5") (pintype "bidirectional"))
      (node (ref "U4") (pin "4") (pinfunction "QE_4") (pintype "output"))
    )
    (net (code "88") (name "SH_6") (class "Default")
      (node (ref "IC1") (pin "6") (pinfunction "I6_6") (pintype "bidirectional"))
      (node (ref "U4") (pin "5") (pinfunction "QF_5") (pintype "output"))
    )
    (net (code "89") (name "SH_7") (class "Default")
      (node (ref "IC1") (pin "7") (pinfunction "I7_7") (pintype "bidirectional"))
      (node (ref "U4") (pin "6") (pinfunction "QG_6") (pintype "output"))
    )
    (net (code "90") (name "SH_8") (class "Default")
      (node (ref "IC1") (pin "8") (pinfunction "I8_8") (pintype "bidirectional"))
      (node (ref "U4") (pin "7") (pinfunction "QH_7") (pintype "output"))
    )
    (net (code "91") (name "SH_CLK") (class "Default")
      (node (ref "J7") (pin "4") (pinfunction "4_4") (pintype "passive"))
      (node (ref "U$1") (pin "6") (pinfunction "IO16_6") (pintype "bidirectional"))
      (node (ref "U4") (pin "11") (pinfunction "SHIFTCLOCK_11") (pintype "input"))
    )
    (net (code "92") (name "SH_DATA") (class "Default")
      (node (ref "U$1") (pin "5") (pinfunction "IO4_5") (pintype "bidirectional"))
      (node (ref "U4") (pin "14") (pinfunction "A_14") (pintype "input"))
    )
    (net (code "93") (name "SH_DATA_OUT") (class "Default")
      (node (ref "J7") (pin "3") (pinfunction "3_3") (pintype "passive"))
      (node (ref "U4") (pin "9") (pinfunction "SQH_9") (pintype "output"))
    )
    (net (code "94") (name "SH_LATCH") (class "Default")
      (node (ref "J7") (pin "5") (pinfunction "5_5") (pintype "passive"))
      (node (ref "U$1") (pin "4") (pinfunction "IO2_4") (pintype "bidirectional"))
      (node (ref "U4") (pin "12") (pinfunction "LATCHCLOCK_12") (pintype "input"))
    )
    (net (code "95") (name "unconnected-(LED-DATA_OUT-Pad4)") (class "Default")
      (node (ref "LED") (pin "4") (pinfunction "DATA_OUT_4") (pintype "bidirectional"))
    )
    (net (code "96") (name "unconnected-(U$1-IO1-Pad13)") (class "Default")
      (node (ref "U$1") (pin "13") (pinfunction "IO1_13") (pintype "bidirectional"))
    )
    (net (code "97") (name "unconnected-(U$1-IO3-Pad12)") (class "Default")
      (node (ref "U$1") (pin "12") (pinfunction "IO3_12") (pintype "bidirectional"))
    )
    (net (code "98") (name "unconnected-(U$1-IO5-Pad8)") (class "Default")
      (node (ref "U$1") (pin "8") (pinfunction "IO5_8") (pintype "bidirectional"))
    )
    (net (code "99") (name "unconnected-(U$1-IO19-Pad10)") (class "Default")
      (node (ref "U$1") (pin "10") (pinfunction "IO19_10") (pintype "bidirectional"))
    )
    (net (code "100") (name "unconnected-(U2-NC-Pad12)") (class "Default")
      (node (ref "U2") (pin "12") (pinfunction "NC_12") (pintype "passive"))
    )
    (net (code "101") (name "unconnected-(U2-NC_2-Pad1)") (class "Default")
      (node (ref "U2") (pin "1") (pinfunction "NC_2_1") (pintype "passive"))
    )
    (net (code "102") (name "unconnected-(U2-NC_3-Pad2)") (class "Default")
      (node (ref "U2") (pin "2") (pinfunction "NC_3_2") (pintype "passive"))
    )
    (net (code "103") (name "unconnected-(U3-NC-Pad12)") (class "Default")
      (node (ref "U3") (pin "12") (pinfunction "NC_12") (pintype "passive"))
    )
    (net (code "104") (name "unconnected-(U3-NC_2-Pad1)") (class "Default")
      (node (ref "U3") (pin "1") (pinfunction "NC_2_1") (pintype "passive"))
    )
    (net (code "105") (name "unconnected-(U3-NC_3-Pad2)") (class "Default")
      (node (ref "U3") (pin "2") (pinfunction "NC_3_2") (pintype "passive"))
    )
  )
)
